# CleanOpampBoostPedal.net
KiCad netlist of a schematic drawn in EAGLE
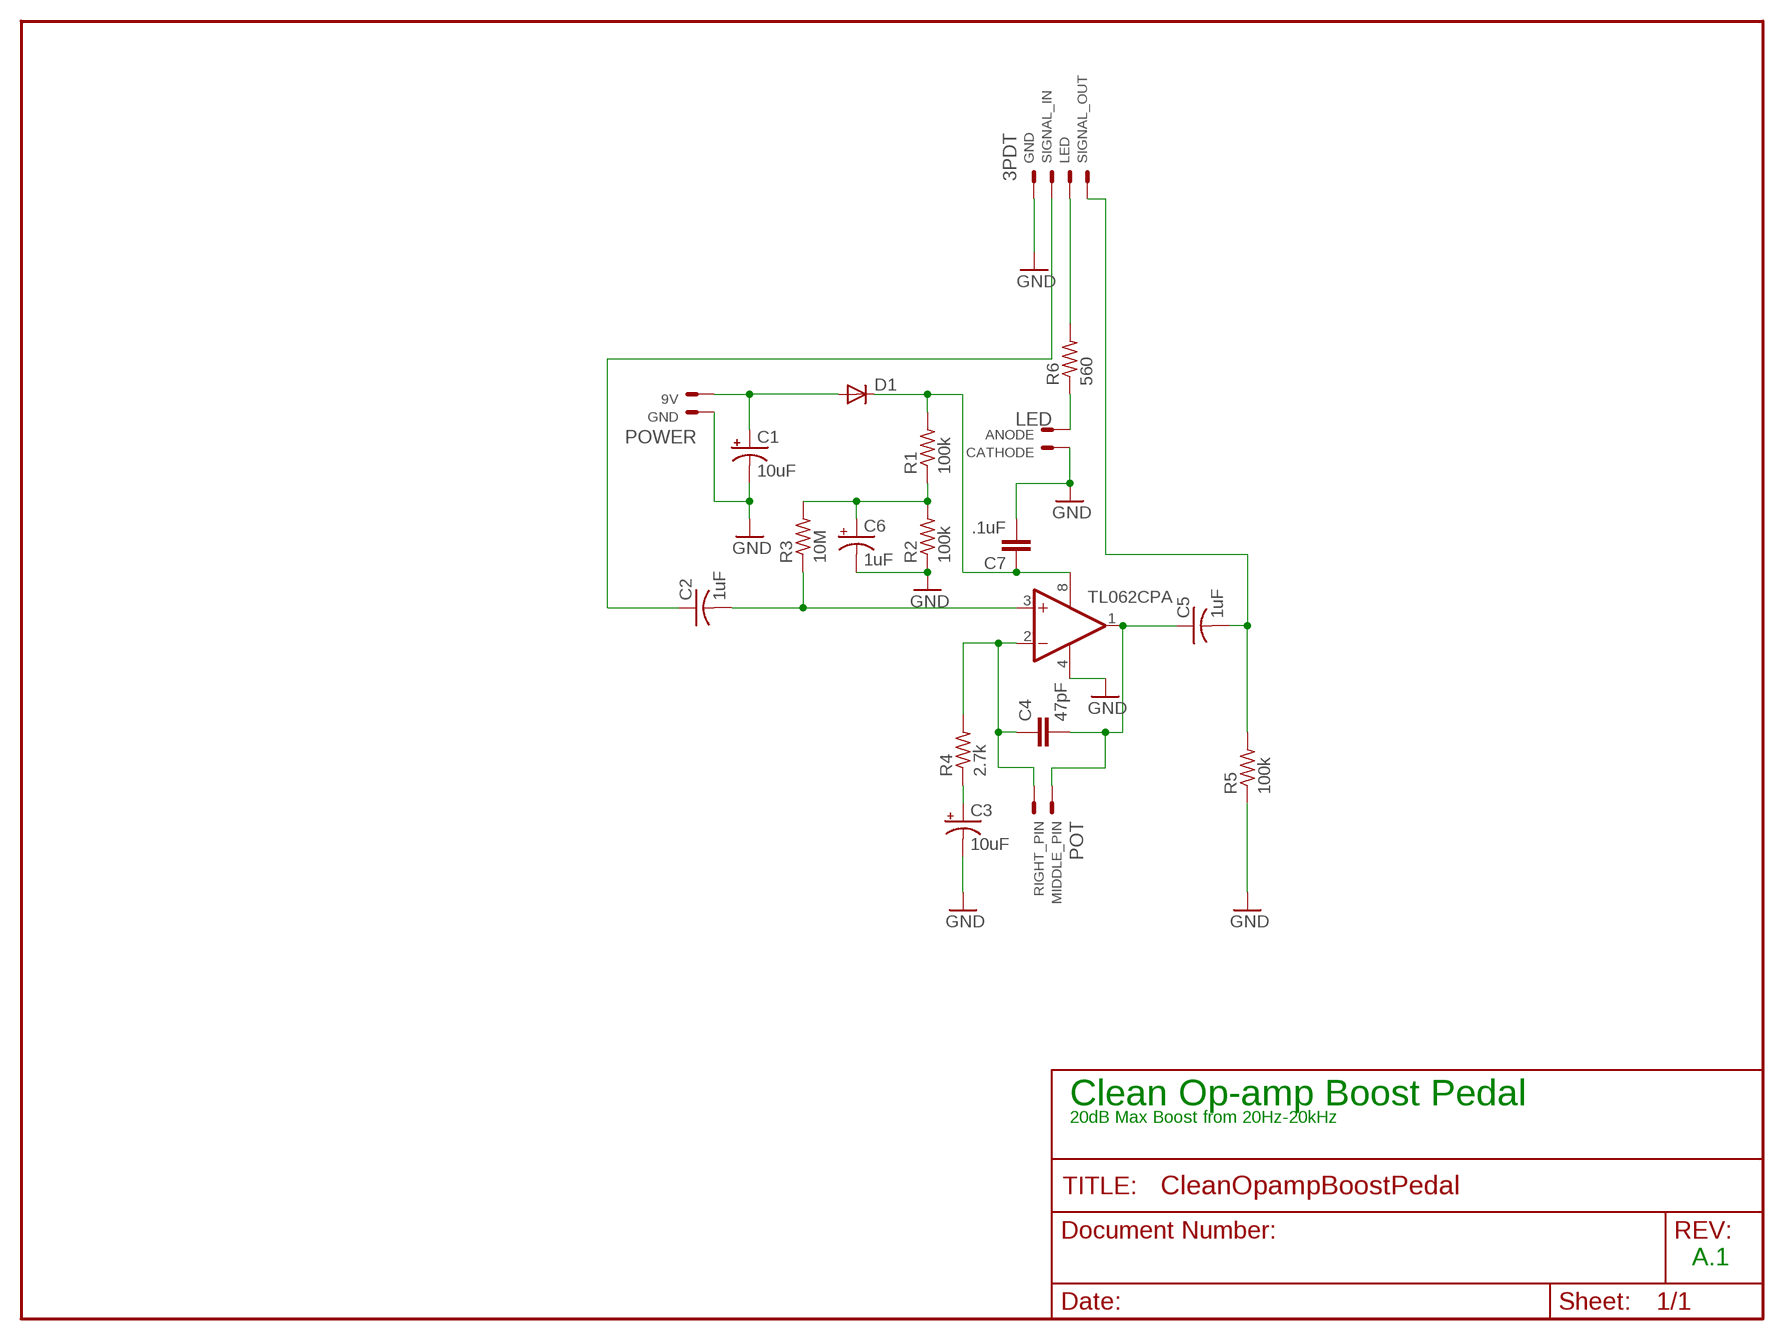
[diagram p0: schematic, sheet 1]

(export (version "E")
  (design (tool "Eeschema 10.0.6"))
  (components
    (comp (ref "3PDT")
      (value "22-23-2041")
      (footprint "eagle-import:22-23-2041")
      (fields (field (name "TEMP") "3PDT"))
      (libsource (lib "eagle-import") (part "22-23-2041"))
    )
    (comp (ref "C1")
      (value "10uF")
      (footprint "eagle-import:E2,5-6E")
      (libsource (lib "eagle-import") (part "CPOL-USE2,5-6E"))
    )
    (comp (ref "C2")
      (value "1uF")
      (footprint "eagle-import:C050-045X075")
      (libsource (lib "eagle-import") (part "C-US050-045X075"))
    )
    (comp (ref "C3")
      (value "10uF")
      (footprint "eagle-import:E2,5-6E")
      (libsource (lib "eagle-import") (part "CPOL-USE2,5-6E"))
    )
    (comp (ref "C4")
      (value "47pF")
      (footprint "eagle-import:C2.5-2")
      (libsource (lib "eagle-import") (part "C2.5/2"))
    )
    (comp (ref "C5")
      (value "1uF")
      (footprint "eagle-import:C050-045X075")
      (libsource (lib "eagle-import") (part "C-US050-045X075"))
    )
    (comp (ref "C6")
      (value "1uF")
      (footprint "eagle-import:E2,5-6")
      (libsource (lib "eagle-import") (part "CPOL-USE2.5-6"))
    )
    (comp (ref "C7")
      (value ".1uF")
      (footprint "eagle-import:C2.5-2")
      (libsource (lib "eagle-import") (part "C2.5/2"))
    )
    (comp (ref "D1")
      (value "DIODE-D-2.5")
      (footprint "eagle-import:D-2.5")
      (libsource (lib "eagle-import") (part "DIODE-D-2.5"))
    )
    (comp (ref "LED")
      (value "22-23-2021")
      (footprint "eagle-import:22-23-2021")
      (libsource (lib "eagle-import") (part "22-23-2021"))
    )
    (comp (ref "POT")
      (value "22-23-2021")
      (footprint "eagle-import:22-23-2021")
      (libsource (lib "eagle-import") (part "22-23-2021"))
    )
    (comp (ref "POWER")
      (value "22-23-2021")
      (footprint "eagle-import:22-23-2021")
      (libsource (lib "eagle-import") (part "22-23-2021"))
    )
    (comp (ref "R1")
      (value "100k")
      (footprint "eagle-import:0207_2V")
      (libsource (lib "eagle-import") (part "R-US_0207/2V"))
    )
    (comp (ref "R2")
      (value "100k")
      (footprint "eagle-import:0207_2V")
      (libsource (lib "eagle-import") (part "R-US_0207/2V"))
    )
    (comp (ref "R3")
      (value "10M")
      (footprint "eagle-import:0207_2V")
      (libsource (lib "eagle-import") (part "R-US_0207/2V"))
    )
    (comp (ref "R4")
      (value "2.7k")
      (footprint "eagle-import:0207_2V")
      (libsource (lib "eagle-import") (part "R-US_0207/2V"))
    )
    (comp (ref "R5")
      (value "100k")
      (footprint "eagle-import:0207_2V")
      (libsource (lib "eagle-import") (part "R-US_0207/2V"))
    )
    (comp (ref "R6")
      (value "560")
      (footprint "eagle-import:0207_2V")
      (libsource (lib "eagle-import") (part "R-US_0207/2V"))
    )
    (comp (ref "TL062CP")
      (value "LM1458N")
      (footprint "eagle-import:DIL08")
      (libsource (lib "eagle-import") (part "1458NLM"))
    )
  )
  (nets
    (net (code "1") (name "GND") (class "Default")
      (node (ref "3PDT") (pin "1") (pinfunction "S_1") (pintype "passive"))
      (node (ref "C1") (pin "-") (pinfunction "-_-") (pintype "passive"))
      (node (ref "C3") (pin "-") (pinfunction "-_-") (pintype "passive"))
      (node (ref "C6") (pin "-") (pinfunction "-_-") (pintype "passive"))
      (node (ref "C7") (pin "2") (pinfunction "2_2") (pintype "passive"))
      (node (ref "LED") (pin "1") (pinfunction "S_1") (pintype "passive"))
      (node (ref "POWER") (pin "1") (pinfunction "S_1") (pintype "passive"))
      (node (ref "R2") (pin "1") (pinfunction "1_1") (pintype "passive"))
      (node (ref "R5") (pin "1") (pinfunction "1_1") (pintype "passive"))
      (node (ref "TL062CP") (pin "4") (pinfunction "V-_4") (pintype "power_in"))
    )
    (net (code "2") (name "Net-(3PDTB-S)") (class "Default")
      (node (ref "3PDT") (pin "2") (pinfunction "S_2") (pintype "passive"))
      (node (ref "C2") (pin "1") (pinfunction "1_1") (pintype "passive"))
    )
    (net (code "3") (name "Net-(3PDTC-S)") (class "Default")
      (node (ref "3PDT") (pin "3") (pinfunction "S_3") (pintype "passive"))
      (node (ref "R6") (pin "2") (pinfunction "2_2") (pintype "passive"))
    )
    (net (code "4") (name "Net-(3PDTD-S)") (class "Default")
      (node (ref "3PDT") (pin "4") (pinfunction "S_4") (pintype "passive"))
      (node (ref "C5") (pin "2") (pinfunction "2_2") (pintype "passive"))
      (node (ref "R5") (pin "2") (pinfunction "2_2") (pintype "passive"))
    )
    (net (code "5") (name "Net-(C3-Pad+)") (class "Default")
      (node (ref "C3") (pin "+") (pinfunction "+_+") (pintype "passive"))
      (node (ref "R4") (pin "1") (pinfunction "1_1") (pintype "passive"))
    )
    (net (code "6") (name "Net-(C6-Pad+)") (class "Default")
      (node (ref "C6") (pin "+") (pinfunction "+_+") (pintype "passive"))
      (node (ref "R1") (pin "1") (pinfunction "1_1") (pintype "passive"))
      (node (ref "R2") (pin "2") (pinfunction "2_2") (pintype "passive"))
      (node (ref "R3") (pin "2") (pinfunction "2_2") (pintype "passive"))
    )
    (net (code "7") (name "Net-(LEDB-S)") (class "Default")
      (node (ref "LED") (pin "2") (pinfunction "S_2") (pintype "passive"))
      (node (ref "R6") (pin "1") (pinfunction "1_1") (pintype "passive"))
    )
    (net (code "8") (name "Net-(POTA-S)") (class "Default")
      (node (ref "C4") (pin "2") (pinfunction "2_2") (pintype "passive"))
      (node (ref "C5") (pin "1") (pinfunction "1_1") (pintype "passive"))
      (node (ref "POT") (pin "1") (pinfunction "S_1") (pintype "passive"))
      (node (ref "TL062CP") (pin "1") (pinfunction "OUT_1") (pintype "output"))
    )
    (net (code "9") (name "Net-(POTB-S)") (class "Default")
      (node (ref "C4") (pin "1") (pinfunction "1_1") (pintype "passive"))
      (node (ref "POT") (pin "2") (pinfunction "S_2") (pintype "passive"))
      (node (ref "R4") (pin "2") (pinfunction "2_2") (pintype "passive"))
      (node (ref "TL062CP") (pin "2") (pinfunction "-IN_2") (pintype "input"))
    )
    (net (code "10") (name "Net-(POWERB-S)") (class "Default")
      (node (ref "C1") (pin "+") (pinfunction "+_+") (pintype "passive"))
      (node (ref "D1") (pin "A") (pinfunction "A_A") (pintype "passive"))
      (node (ref "POWER") (pin "2") (pinfunction "S_2") (pintype "passive"))
    )
    (net (code "11") (name "Net-(TL062CPA-+IN)") (class "Default")
      (node (ref "C2") (pin "2") (pinfunction "2_2") (pintype "passive"))
      (node (ref "R3") (pin "1") (pinfunction "1_1") (pintype "passive"))
      (node (ref "TL062CP") (pin "3") (pinfunction "+IN_3") (pintype "input"))
    )
    (net (code "12") (name "Net-(TL062CPC-V+)") (class "Default")
      (node (ref "C7") (pin "1") (pinfunction "1_1") (pintype "passive"))
      (node (ref "D1") (pin "C") (pinfunction "C_C") (pintype "passive"))
      (node (ref "R1") (pin "2") (pinfunction "2_2") (pintype "passive"))
      (node (ref "TL062CP") (pin "8") (pinfunction "V+_8") (pintype "power_in"))
    )
  )
)
